# FOCDriver.net
KiCad netlist of a schematic drawn in EAGLE
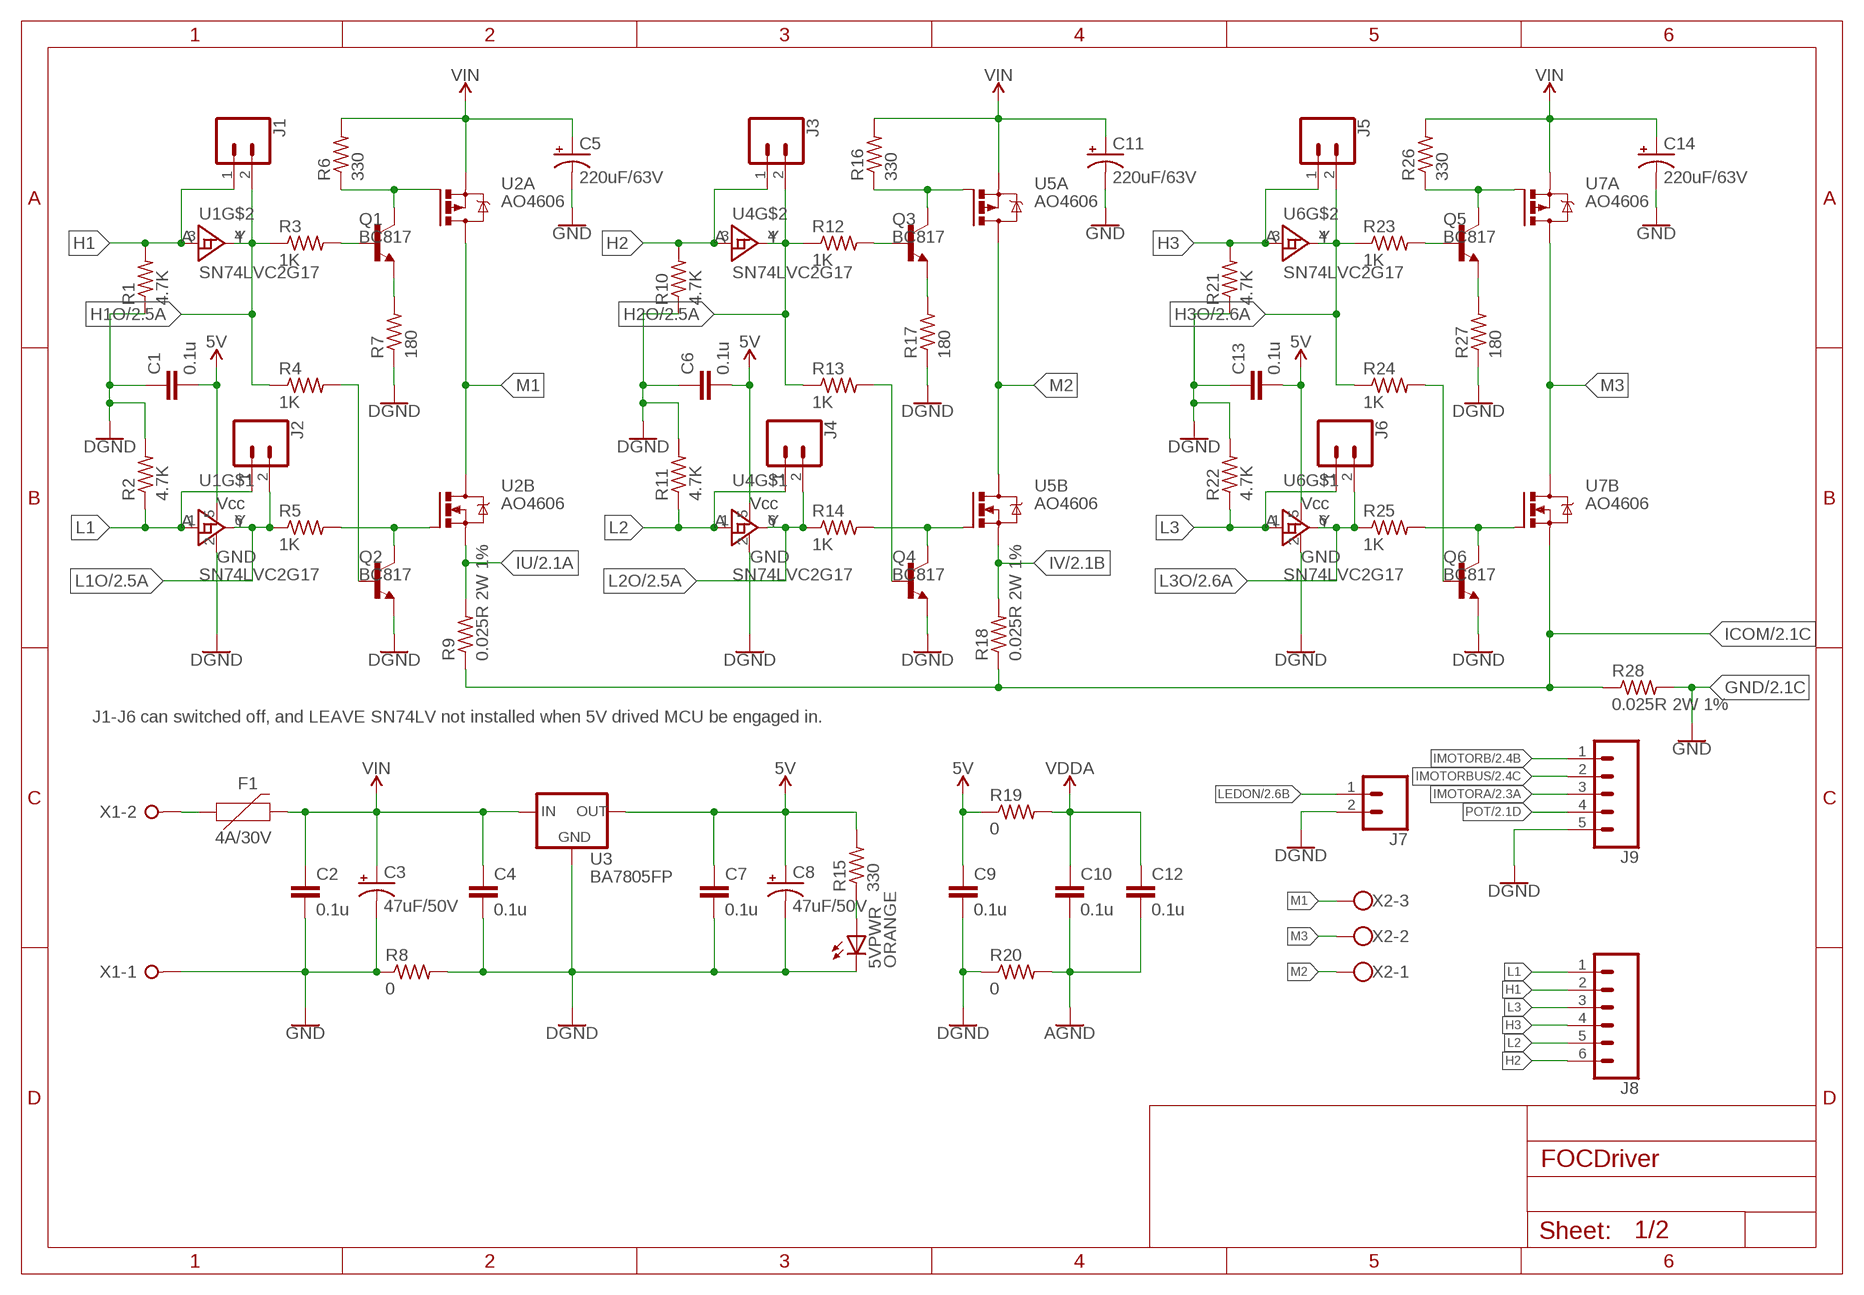
[diagram p0: schematic, sheet 1]
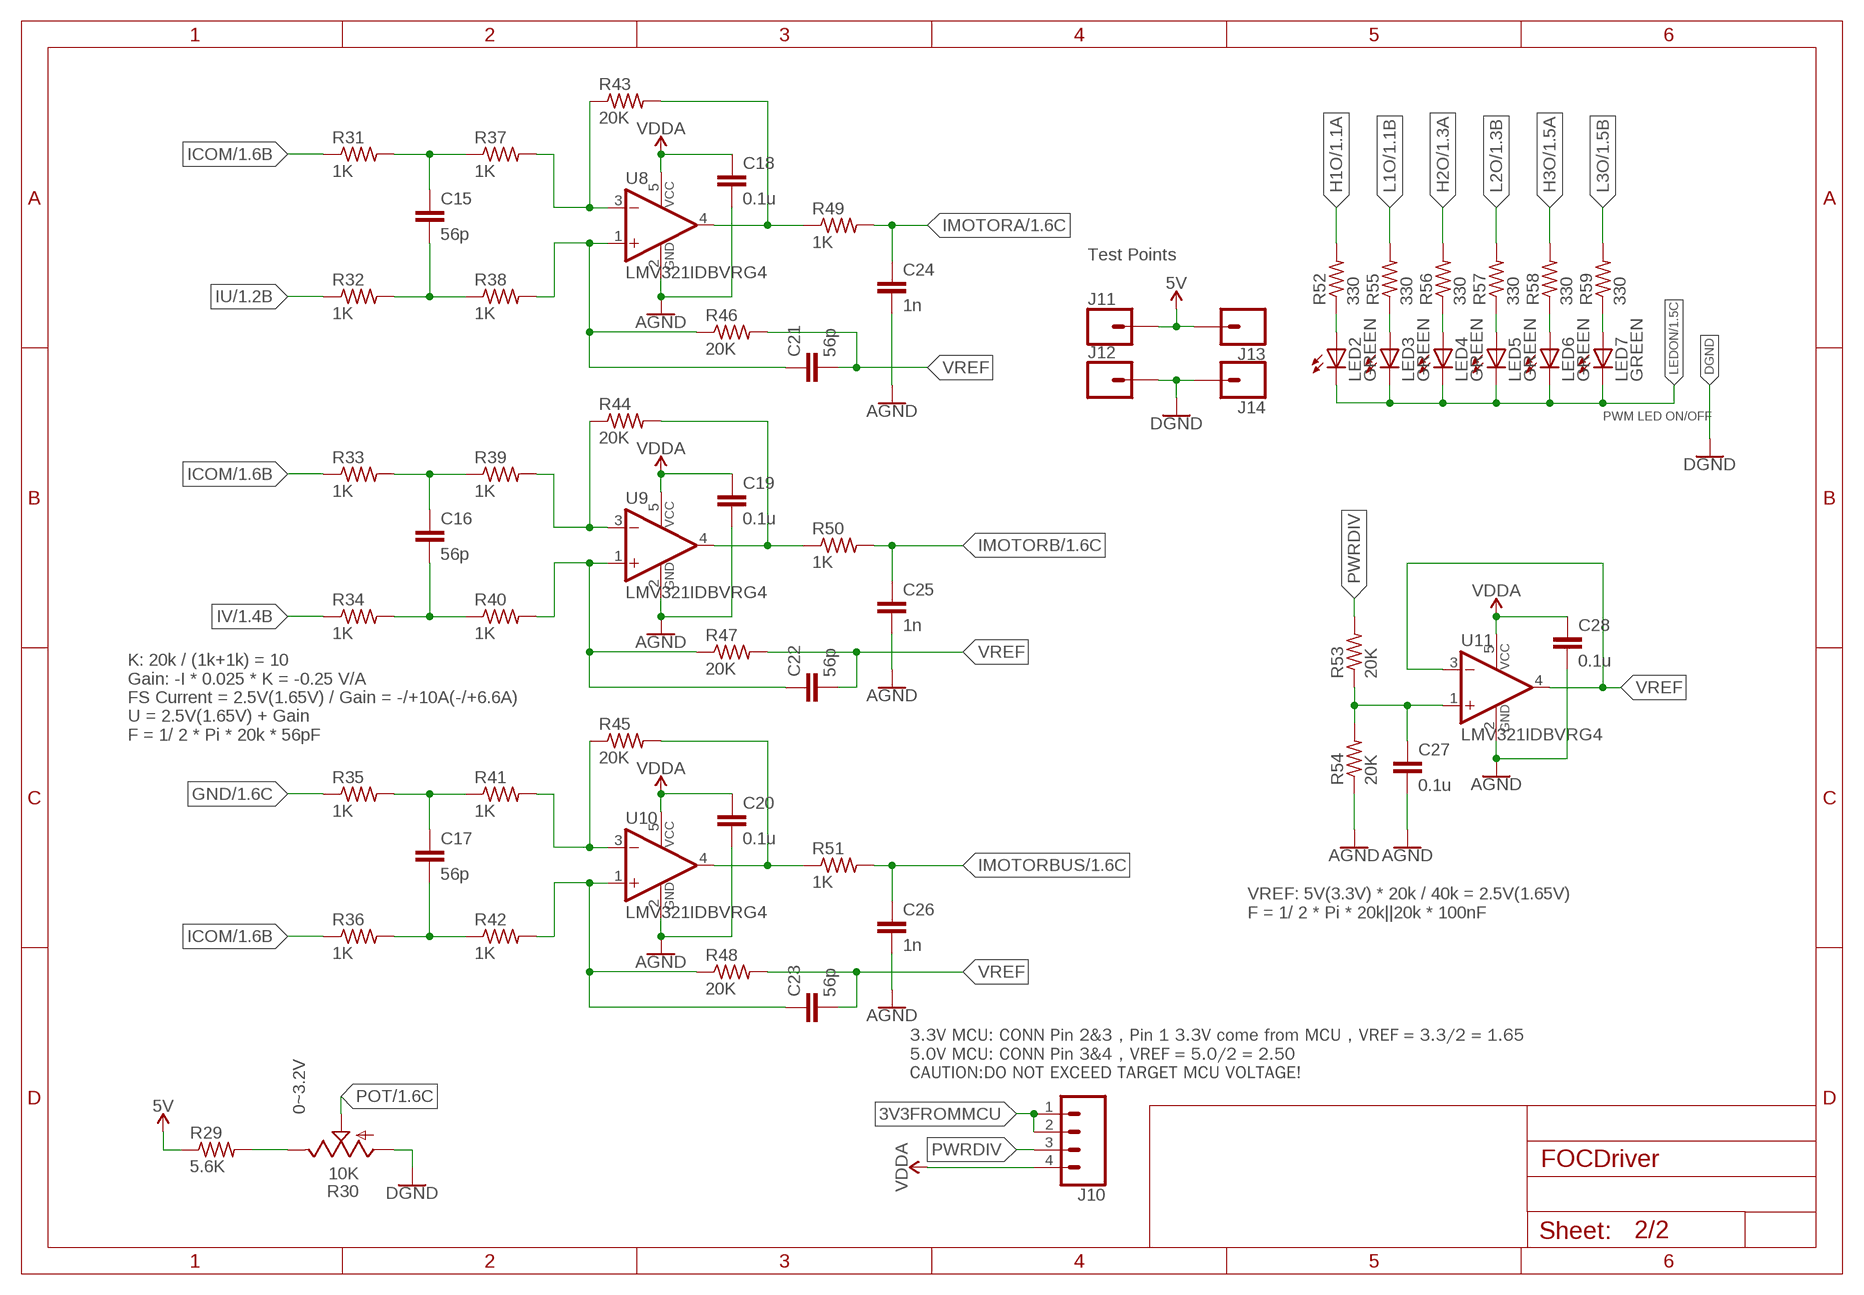
[diagram p1: schematic, sheet 2]

(export (version "E")
  (design (tool "Eeschema 10.0.6"))
  (components
    (comp (ref "C15")
      (value "56p")
      (footprint "eagle-import:C0805")
      (libsource (lib "eagle-import") (part "C-EUC0805"))
    )
    (comp (ref "C16")
      (value "56p")
      (footprint "eagle-import:C0805")
      (libsource (lib "eagle-import") (part "C-EUC0805"))
    )
    (comp (ref "C17")
      (value "56p")
      (footprint "eagle-import:C0805")
      (libsource (lib "eagle-import") (part "C-EUC0805"))
    )
    (comp (ref "C18")
      (value "0.1u")
      (footprint "eagle-import:C0805")
      (libsource (lib "eagle-import") (part "C-EUC0805"))
    )
    (comp (ref "C19")
      (value "0.1u")
      (footprint "eagle-import:C0805")
      (libsource (lib "eagle-import") (part "C-EUC0805"))
    )
    (comp (ref "C20")
      (value "0.1u")
      (footprint "eagle-import:C0805")
      (libsource (lib "eagle-import") (part "C-EUC0805"))
    )
    (comp (ref "C21")
      (value "56p")
      (footprint "eagle-import:C0805")
      (libsource (lib "eagle-import") (part "C-EUC0805"))
    )
    (comp (ref "C22")
      (value "56p")
      (footprint "eagle-import:C0805")
      (libsource (lib "eagle-import") (part "C-EUC0805"))
    )
    (comp (ref "C23")
      (value "56p")
      (footprint "eagle-import:C0805")
      (libsource (lib "eagle-import") (part "C-EUC0805"))
    )
    (comp (ref "C24")
      (value "1n")
      (footprint "eagle-import:C0805")
      (libsource (lib "eagle-import") (part "C-EUC0805"))
    )
    (comp (ref "C25")
      (value "1n")
      (footprint "eagle-import:C0805")
      (libsource (lib "eagle-import") (part "C-EUC0805"))
    )
    (comp (ref "C26")
      (value "1n")
      (footprint "eagle-import:C0805")
      (libsource (lib "eagle-import") (part "C-EUC0805"))
    )
    (comp (ref "C27")
      (value "0.1u")
      (footprint "eagle-import:C0805")
      (libsource (lib "eagle-import") (part "C-EUC0805"))
    )
    (comp (ref "C28")
      (value "0.1u")
      (footprint "eagle-import:C0805")
      (libsource (lib "eagle-import") (part "C-EUC0805"))
    )
    (comp (ref "J10")
      (value "CONN_04")
      (footprint "eagle-import:1X04")
      (libsource (lib "eagle-import") (part "CONN_04"))
    )
    (comp (ref "J11")
      (value "CONN_01PTH_NO_SILK_YES_STOP")
      (footprint "eagle-import:1X01_NO_SILK")
      (libsource (lib "eagle-import") (part "CONN_01PTH_NO_SILK_YES_STOP"))
    )
    (comp (ref "J12")
      (value "CONN_01PTH_NO_SILK_YES_STOP")
      (footprint "eagle-import:1X01_NO_SILK")
      (libsource (lib "eagle-import") (part "CONN_01PTH_NO_SILK_YES_STOP"))
    )
    (comp (ref "J13")
      (value "CONN_01PTH_NO_SILK_YES_STOP")
      (footprint "eagle-import:1X01_NO_SILK")
      (libsource (lib "eagle-import") (part "CONN_01PTH_NO_SILK_YES_STOP"))
    )
    (comp (ref "J14")
      (value "CONN_01PTH_NO_SILK_YES_STOP")
      (footprint "eagle-import:1X01_NO_SILK")
      (libsource (lib "eagle-import") (part "CONN_01PTH_NO_SILK_YES_STOP"))
    )
    (comp (ref "LED2")
      (value "GREEN")
      (footprint "eagle-import:SML0805")
      (libsource (lib "eagle-import") (part "LEDSML0805"))
    )
    (comp (ref "LED3")
      (value "GREEN")
      (footprint "eagle-import:SML0805")
      (libsource (lib "eagle-import") (part "LEDSML0805"))
    )
    (comp (ref "LED4")
      (value "GREEN")
      (footprint "eagle-import:SML0805")
      (libsource (lib "eagle-import") (part "LEDSML0805"))
    )
    (comp (ref "LED5")
      (value "GREEN")
      (footprint "eagle-import:SML0805")
      (libsource (lib "eagle-import") (part "LEDSML0805"))
    )
    (comp (ref "LED6")
      (value "GREEN")
      (footprint "eagle-import:SML0805")
      (libsource (lib "eagle-import") (part "LEDSML0805"))
    )
    (comp (ref "LED7")
      (value "GREEN")
      (footprint "eagle-import:SML0805")
      (libsource (lib "eagle-import") (part "LEDSML0805"))
    )
    (comp (ref "R29")
      (value "5.6K")
      (footprint "eagle-import:R0805")
      (libsource (lib "eagle-import") (part "R-US_R0805"))
    )
    (comp (ref "R30")
      (value "10K")
      (footprint "eagle-import:CT6")
      (libsource (lib "eagle-import") (part "TRIM_US-CT6"))
    )
    (comp (ref "R31")
      (value "1K")
      (footprint "eagle-import:R0805")
      (libsource (lib "eagle-import") (part "R-US_R0805"))
    )
    (comp (ref "R32")
      (value "1K")
      (footprint "eagle-import:R0805")
      (libsource (lib "eagle-import") (part "R-US_R0805"))
    )
    (comp (ref "R33")
      (value "1K")
      (footprint "eagle-import:R0805")
      (libsource (lib "eagle-import") (part "R-US_R0805"))
    )
    (comp (ref "R34")
      (value "1K")
      (footprint "eagle-import:R0805")
      (libsource (lib "eagle-import") (part "R-US_R0805"))
    )
    (comp (ref "R35")
      (value "1K")
      (footprint "eagle-import:R0805")
      (libsource (lib "eagle-import") (part "R-US_R0805"))
    )
    (comp (ref "R36")
      (value "1K")
      (footprint "eagle-import:R0805")
      (libsource (lib "eagle-import") (part "R-US_R0805"))
    )
    (comp (ref "R37")
      (value "1K")
      (footprint "eagle-import:R0805")
      (libsource (lib "eagle-import") (part "R-US_R0805"))
    )
    (comp (ref "R38")
      (value "1K")
      (footprint "eagle-import:R0805")
      (libsource (lib "eagle-import") (part "R-US_R0805"))
    )
    (comp (ref "R39")
      (value "1K")
      (footprint "eagle-import:R0805")
      (libsource (lib "eagle-import") (part "R-US_R0805"))
    )
    (comp (ref "R40")
      (value "1K")
      (footprint "eagle-import:R0805")
      (libsource (lib "eagle-import") (part "R-US_R0805"))
    )
    (comp (ref "R41")
      (value "1K")
      (footprint "eagle-import:R0805")
      (libsource (lib "eagle-import") (part "R-US_R0805"))
    )
    (comp (ref "R42")
      (value "1K")
      (footprint "eagle-import:R0805")
      (libsource (lib "eagle-import") (part "R-US_R0805"))
    )
    (comp (ref "R43")
      (value "20K")
      (footprint "eagle-import:R0805")
      (libsource (lib "eagle-import") (part "R-US_R0805"))
    )
    (comp (ref "R44")
      (value "20K")
      (footprint "eagle-import:R0805")
      (libsource (lib "eagle-import") (part "R-US_R0805"))
    )
    (comp (ref "R45")
      (value "20K")
      (footprint "eagle-import:R0805")
      (libsource (lib "eagle-import") (part "R-US_R0805"))
    )
    (comp (ref "R46")
      (value "20K")
      (footprint "eagle-import:R0805")
      (libsource (lib "eagle-import") (part "R-US_R0805"))
    )
    (comp (ref "R47")
      (value "20K")
      (footprint "eagle-import:R0805")
      (libsource (lib "eagle-import") (part "R-US_R0805"))
    )
    (comp (ref "R48")
      (value "20K")
      (footprint "eagle-import:R0805")
      (libsource (lib "eagle-import") (part "R-US_R0805"))
    )
    (comp (ref "R49")
      (value "1K")
      (footprint "eagle-import:R0805")
      (libsource (lib "eagle-import") (part "R-US_R0805"))
    )
    (comp (ref "R50")
      (value "1K")
      (footprint "eagle-import:R0805")
      (libsource (lib "eagle-import") (part "R-US_R0805"))
    )
    (comp (ref "R51")
      (value "1K")
      (footprint "eagle-import:R0805")
      (libsource (lib "eagle-import") (part "R-US_R0805"))
    )
    (comp (ref "R52")
      (value "330")
      (footprint "eagle-import:R0805")
      (libsource (lib "eagle-import") (part "R-US_R0805"))
    )
    (comp (ref "R53")
      (value "20K")
      (footprint "eagle-import:R0805")
      (libsource (lib "eagle-import") (part "R-US_R0805"))
    )
    (comp (ref "R54")
      (value "20K")
      (footprint "eagle-import:R0805")
      (libsource (lib "eagle-import") (part "R-US_R0805"))
    )
    (comp (ref "R55")
      (value "330")
      (footprint "eagle-import:R0805")
      (libsource (lib "eagle-import") (part "R-US_R0805"))
    )
    (comp (ref "R56")
      (value "330")
      (footprint "eagle-import:R0805")
      (libsource (lib "eagle-import") (part "R-US_R0805"))
    )
    (comp (ref "R57")
      (value "330")
      (footprint "eagle-import:R0805")
      (libsource (lib "eagle-import") (part "R-US_R0805"))
    )
    (comp (ref "R58")
      (value "330")
      (footprint "eagle-import:R0805")
      (libsource (lib "eagle-import") (part "R-US_R0805"))
    )
    (comp (ref "R59")
      (value "330")
      (footprint "eagle-import:R0805")
      (libsource (lib "eagle-import") (part "R-US_R0805"))
    )
    (comp (ref "U8")
      (value "LMV321IDBVRG4")
      (footprint "eagle-import:SOT95P285X120-5N")
      (libsource (lib "eagle-import") (part "LMV321IDBVRG4"))
    )
    (comp (ref "U9")
      (value "LMV321IDBVRG4")
      (footprint "eagle-import:SOT95P285X120-5N")
      (libsource (lib "eagle-import") (part "LMV321IDBVRG4"))
    )
    (comp (ref "U10")
      (value "LMV321IDBVRG4")
      (footprint "eagle-import:SOT95P285X120-5N")
      (libsource (lib "eagle-import") (part "LMV321IDBVRG4"))
    )
    (comp (ref "U11")
      (value "LMV321IDBVRG4")
      (footprint "eagle-import:SOT95P285X120-5N")
      (libsource (lib "eagle-import") (part "LMV321IDBVRG4"))
    )
    (comp (ref "5VPWR")
      (value "ORANGE")
      (footprint "eagle-import:SML0805")
      (libsource (lib "eagle-import") (part "LEDSML0805"))
    )
    (comp (ref "C1")
      (value "0.1u")
      (footprint "eagle-import:C0805")
      (libsource (lib "eagle-import") (part "C-EUC0805"))
    )
    (comp (ref "C2")
      (value "0.1u")
      (footprint "eagle-import:C0805")
      (libsource (lib "eagle-import") (part "C-EUC0805"))
    )
    (comp (ref "C3")
      (value "47uF/50V")
      (footprint "eagle-import:E2,5-7")
      (libsource (lib "eagle-import") (part "CPOL-USE2.5-7"))
    )
    (comp (ref "C4")
      (value "0.1u")
      (footprint "eagle-import:C0805")
      (libsource (lib "eagle-import") (part "C-EUC0805"))
    )
    (comp (ref "C5")
      (value "220uF/63V")
      (footprint "eagle-import:E5-10,5")
      (libsource (lib "eagle-import") (part "CPOL-USE5-10.5"))
    )
    (comp (ref "C6")
      (value "0.1u")
      (footprint "eagle-import:C0805")
      (libsource (lib "eagle-import") (part "C-EUC0805"))
    )
    (comp (ref "C7")
      (value "0.1u")
      (footprint "eagle-import:C0805")
      (libsource (lib "eagle-import") (part "C-EUC0805"))
    )
    (comp (ref "C8")
      (value "47uF/50V")
      (footprint "eagle-import:E2,5-7")
      (libsource (lib "eagle-import") (part "CPOL-USE2.5-7"))
    )
    (comp (ref "C9")
      (value "0.1u")
      (footprint "eagle-import:C0805")
      (libsource (lib "eagle-import") (part "C-EUC0805"))
    )
    (comp (ref "C10")
      (value "0.1u")
      (footprint "eagle-import:C0805")
      (libsource (lib "eagle-import") (part "C-EUC0805"))
    )
    (comp (ref "C11")
      (value "220uF/63V")
      (footprint "eagle-import:E5-10,5")
      (libsource (lib "eagle-import") (part "CPOL-USE5-10.5"))
    )
    (comp (ref "C12")
      (value "0.1u")
      (footprint "eagle-import:C0805")
      (libsource (lib "eagle-import") (part "C-EUC0805"))
    )
    (comp (ref "C13")
      (value "0.1u")
      (footprint "eagle-import:C0805")
      (libsource (lib "eagle-import") (part "C-EUC0805"))
    )
    (comp (ref "C14")
      (value "220uF/63V")
      (footprint "eagle-import:E5-10,5")
      (libsource (lib "eagle-import") (part "CPOL-USE5-10.5"))
    )
    (comp (ref "F1")
      (value "4A/30V")
      (footprint "eagle-import:PTH")
      (libsource (lib "eagle-import") (part "PPTC_PTH"))
    )
    (comp (ref "J1")
      (value "CONN_02")
      (footprint "eagle-import:1X02")
      (libsource (lib "eagle-import") (part "CONN_02"))
    )
    (comp (ref "J2")
      (value "CONN_02")
      (footprint "eagle-import:1X02")
      (libsource (lib "eagle-import") (part "CONN_02"))
    )
    (comp (ref "J3")
      (value "CONN_02")
      (footprint "eagle-import:1X02")
      (libsource (lib "eagle-import") (part "CONN_02"))
    )
    (comp (ref "J4")
      (value "CONN_02")
      (footprint "eagle-import:1X02")
      (libsource (lib "eagle-import") (part "CONN_02"))
    )
    (comp (ref "J5")
      (value "CONN_02")
      (footprint "eagle-import:1X02")
      (libsource (lib "eagle-import") (part "CONN_02"))
    )
    (comp (ref "J6")
      (value "CONN_02")
      (footprint "eagle-import:1X02")
      (libsource (lib "eagle-import") (part "CONN_02"))
    )
    (comp (ref "J7")
      (value "CONN_02")
      (footprint "eagle-import:1X02")
      (libsource (lib "eagle-import") (part "CONN_02"))
    )
    (comp (ref "J8")
      (value "CONN_06SILK_FEMALE_PTH")
      (footprint "eagle-import:1X06")
      (libsource (lib "eagle-import") (part "CONN_06SILK_FEMALE_PTH"))
    )
    (comp (ref "J9")
      (value "CONN_05")
      (footprint "eagle-import:1X05")
      (libsource (lib "eagle-import") (part "CONN_05"))
    )
    (comp (ref "Q1")
      (value "BC817")
      (footprint "eagle-import:SOT23-BEC")
      (libsource (lib "eagle-import") (part "BC817SMD-40"))
    )
    (comp (ref "Q2")
      (value "BC817")
      (footprint "eagle-import:SOT23-BEC")
      (libsource (lib "eagle-import") (part "BC817SMD-40"))
    )
    (comp (ref "Q3")
      (value "BC817")
      (footprint "eagle-import:SOT23-BEC")
      (libsource (lib "eagle-import") (part "BC817SMD-40"))
    )
    (comp (ref "Q4")
      (value "BC817")
      (footprint "eagle-import:SOT23-BEC")
      (libsource (lib "eagle-import") (part "BC817SMD-40"))
    )
    (comp (ref "Q5")
      (value "BC817")
      (footprint "eagle-import:SOT23-BEC")
      (libsource (lib "eagle-import") (part "BC817SMD-40"))
    )
    (comp (ref "Q6")
      (value "BC817")
      (footprint "eagle-import:SOT23-BEC")
      (libsource (lib "eagle-import") (part "BC817SMD-40"))
    )
    (comp (ref "R1")
      (value "4.7K")
      (footprint "eagle-import:R0805")
      (libsource (lib "eagle-import") (part "R-US_R0805"))
    )
    (comp (ref "R2")
      (value "4.7K")
      (footprint "eagle-import:R0805")
      (libsource (lib "eagle-import") (part "R-US_R0805"))
    )
    (comp (ref "R3")
      (value "1K")
      (footprint "eagle-import:R0805")
      (libsource (lib "eagle-import") (part "R-US_R0805"))
    )
    (comp (ref "R4")
      (value "1K")
      (footprint "eagle-import:R0805")
      (libsource (lib "eagle-import") (part "R-US_R0805"))
    )
    (comp (ref "R5")
      (value "1K")
      (footprint "eagle-import:R0805")
      (libsource (lib "eagle-import") (part "R-US_R0805"))
    )
    (comp (ref "R6")
      (value "330")
      (footprint "eagle-import:R0805")
      (libsource (lib "eagle-import") (part "R-US_R0805"))
    )
    (comp (ref "R7")
      (value "180")
      (footprint "eagle-import:R0805")
      (libsource (lib "eagle-import") (part "R-US_R0805"))
    )
    (comp (ref "R8")
      (value "0")
      (footprint "eagle-import:R0805")
      (libsource (lib "eagle-import") (part "R-US_R0805"))
    )
    (comp (ref "R9")
      (value "0.025R 2W 1%")
      (footprint "eagle-import:R2512")
      (libsource (lib "eagle-import") (part "resistor_R-US_R2512"))
    )
    (comp (ref "R10")
      (value "4.7K")
      (footprint "eagle-import:R0805")
      (libsource (lib "eagle-import") (part "R-US_R0805"))
    )
    (comp (ref "R11")
      (value "4.7K")
      (footprint "eagle-import:R0805")
      (libsource (lib "eagle-import") (part "R-US_R0805"))
    )
    (comp (ref "R12")
      (value "1K")
      (footprint "eagle-import:R0805")
      (libsource (lib "eagle-import") (part "R-US_R0805"))
    )
    (comp (ref "R13")
      (value "1K")
      (footprint "eagle-import:R0805")
      (libsource (lib "eagle-import") (part "R-US_R0805"))
    )
    (comp (ref "R14")
      (value "1K")
      (footprint "eagle-import:R0805")
      (libsource (lib "eagle-import") (part "R-US_R0805"))
    )
    (comp (ref "R15")
      (value "330")
      (footprint "eagle-import:R0805")
      (libsource (lib "eagle-import") (part "R-US_R0805"))
    )
    (comp (ref "R16")
      (value "330")
      (footprint "eagle-import:R0805")
      (libsource (lib "eagle-import") (part "R-US_R0805"))
    )
    (comp (ref "R17")
      (value "180")
      (footprint "eagle-import:R0805")
      (libsource (lib "eagle-import") (part "R-US_R0805"))
    )
    (comp (ref "R18")
      (value "0.025R 2W 1%")
      (footprint "eagle-import:R2512")
      (libsource (lib "eagle-import") (part "resistor_R-US_R2512"))
    )
    (comp (ref "R19")
      (value "0")
      (footprint "eagle-import:R0805")
      (libsource (lib "eagle-import") (part "R-US_R0805"))
    )
    (comp (ref "R20")
      (value "0")
      (footprint "eagle-import:R0805")
      (libsource (lib "eagle-import") (part "R-US_R0805"))
    )
    (comp (ref "R21")
      (value "4.7K")
      (footprint "eagle-import:R0805")
      (libsource (lib "eagle-import") (part "R-US_R0805"))
    )
    (comp (ref "R22")
      (value "4.7K")
      (footprint "eagle-import:R0805")
      (libsource (lib "eagle-import") (part "R-US_R0805"))
    )
    (comp (ref "R23")
      (value "1K")
      (footprint "eagle-import:R0805")
      (libsource (lib "eagle-import") (part "R-US_R0805"))
    )
    (comp (ref "R24")
      (value "1K")
      (footprint "eagle-import:R0805")
      (libsource (lib "eagle-import") (part "R-US_R0805"))
    )
    (comp (ref "R25")
      (value "1K")
      (footprint "eagle-import:R0805")
      (libsource (lib "eagle-import") (part "R-US_R0805"))
    )
    (comp (ref "R26")
      (value "330")
      (footprint "eagle-import:R0805")
      (libsource (lib "eagle-import") (part "R-US_R0805"))
    )
    (comp (ref "R27")
      (value "180")
      (footprint "eagle-import:R0805")
      (libsource (lib "eagle-import") (part "R-US_R0805"))
    )
    (comp (ref "R28")
      (value "0.025R 2W 1%")
      (footprint "eagle-import:R2512")
      (libsource (lib "eagle-import") (part "resistor_R-US_R2512"))
    )
    (comp (ref "U1")
      (value "SN74LVC2G17")
      (footprint "eagle-import:SOT23-6")
      (libsource (lib "eagle-import") (part "SN74LVC2G17"))
    )
    (comp (ref "U2")
      (value "AO4606")
      (footprint "eagle-import:SO08")
      (libsource (lib "eagle-import") (part "AO4606"))
    )
    (comp (ref "U3")
      (value "BA7805FP")
      (footprint "eagle-import:TO-252")
      (libsource (lib "eagle-import") (part "V_REG_78XX7812"))
    )
    (comp (ref "U4")
      (value "SN74LVC2G17")
      (footprint "eagle-import:SOT23-6")
      (libsource (lib "eagle-import") (part "SN74LVC2G17"))
    )
    (comp (ref "U5")
      (value "AO4606")
      (footprint "eagle-import:SO08")
      (libsource (lib "eagle-import") (part "AO4606"))
    )
    (comp (ref "U6")
      (value "SN74LVC2G17")
      (footprint "eagle-import:SOT23-6")
      (libsource (lib "eagle-import") (part "SN74LVC2G17"))
    )
    (comp (ref "U7")
      (value "AO4606")
      (footprint "eagle-import:SO08")
      (libsource (lib "eagle-import") (part "AO4606"))
    )
    (comp (ref "X1")
      (value "W237-02P")
      (footprint "eagle-import:W237-132")
      (libsource (lib "eagle-import") (part "W237-02P"))
    )
    (comp (ref "X2")
      (value "W237-103")
      (footprint "eagle-import:W237-103")
      (fields (field (name "MPN") "237-103"))
      (libsource (lib "eagle-import") (part "W237-103"))
    )
  )
  (nets
    (net (code "1") (name "3V3FROMMCU") (class "Default")
      (node (ref "J10") (pin "1") (pinfunction "1_1") (pintype "passive"))
      (node (ref "J10") (pin "2") (pinfunction "2_2") (pintype "passive"))
    )
    (net (code "2") (name "5V") (class "Default")
      (node (ref "C1") (pin "2") (pinfunction "2_2") (pintype "passive"))
      (node (ref "C13") (pin "2") (pinfunction "2_2") (pintype "passive"))
      (node (ref "C6") (pin "2") (pinfunction "2_2") (pintype "passive"))
      (node (ref "C7") (pin "1") (pinfunction "1_1") (pintype "passive"))
      (node (ref "C8") (pin "+") (pinfunction "+_+") (pintype "passive"))
      (node (ref "C9") (pin "1") (pinfunction "1_1") (pintype "passive"))
      (node (ref "J11") (pin "1") (pinfunction "1_1") (pintype "passive"))
      (node (ref "J13") (pin "1") (pinfunction "1_1") (pintype "passive"))
      (node (ref "R15") (pin "2") (pinfunction "2_2") (pintype "passive"))
      (node (ref "R19") (pin "1") (pinfunction "1_1") (pintype "passive"))
      (node (ref "R29") (pin "1") (pinfunction "1_1") (pintype "passive"))
      (node (ref "U1") (pin "5") (pinfunction "VCC_5") (pintype "power_in"))
      (node (ref "U3") (pin "2") (pinfunction "OUT_2") (pintype "passive"))
      (node (ref "U4") (pin "5") (pinfunction "VCC_5") (pintype "power_in"))
      (node (ref "U6") (pin "5") (pinfunction "VCC_5") (pintype "power_in"))
    )
    (net (code "3") (name "AGND") (class "Default")
      (node (ref "C10") (pin "2") (pinfunction "2_2") (pintype "passive"))
      (node (ref "C12") (pin "2") (pinfunction "2_2") (pintype "passive"))
      (node (ref "C18") (pin "2") (pinfunction "2_2") (pintype "passive"))
      (node (ref "C19") (pin "2") (pinfunction "2_2") (pintype "passive"))
      (node (ref "C20") (pin "2") (pinfunction "2_2") (pintype "passive"))
      (node (ref "C24") (pin "2") (pinfunction "2_2") (pintype "passive"))
      (node (ref "C25") (pin "2") (pinfunction "2_2") (pintype "passive"))
      (node (ref "C26") (pin "2") (pinfunction "2_2") (pintype "passive"))
      (node (ref "C27") (pin "2") (pinfunction "2_2") (pintype "passive"))
      (node (ref "C28") (pin "2") (pinfunction "2_2") (pintype "passive"))
      (node (ref "R20") (pin "2") (pinfunction "2_2") (pintype "passive"))
      (node (ref "R54") (pin "1") (pinfunction "1_1") (pintype "passive"))
      (node (ref "U10") (pin "2") (pinfunction "GND_2") (pintype "power_in"))
      (node (ref "U11") (pin "2") (pinfunction "GND_2") (pintype "power_in"))
      (node (ref "U8") (pin "2") (pinfunction "GND_2") (pintype "power_in"))
      (node (ref "U9") (pin "2") (pinfunction "GND_2") (pintype "power_in"))
    )
    (net (code "4") (name "DGND") (class "Default")
      (node (ref "5VPWR") (pin "C") (pinfunction "C_C") (pintype "passive"))
      (node (ref "C1") (pin "1") (pinfunction "1_1") (pintype "passive"))
      (node (ref "C13") (pin "1") (pinfunction "1_1") (pintype "passive"))
      (node (ref "C4") (pin "2") (pinfunction "2_2") (pintype "passive"))
      (node (ref "C6") (pin "1") (pinfunction "1_1") (pintype "passive"))
      (node (ref "C7") (pin "2") (pinfunction "2_2") (pintype "passive"))
      (node (ref "C8") (pin "-") (pinfunction "-_-") (pintype "passive"))
      (node (ref "C9") (pin "2") (pinfunction "2_2") (pintype "passive"))
      (node (ref "J12") (pin "1") (pinfunction "1_1") (pintype "passive"))
      (node (ref "J14") (pin "1") (pinfunction "1_1") (pintype "passive"))
      (node (ref "J7") (pin "2") (pinfunction "2_2") (pintype "passive"))
      (node (ref "J9") (pin "5") (pinfunction "5_5") (pintype "passive"))
      (node (ref "Q2") (pin "E") (pinfunction "E_E") (pintype "passive"))
      (node (ref "Q4") (pin "E") (pinfunction "E_E") (pintype "passive"))
      (node (ref "Q6") (pin "E") (pinfunction "E_E") (pintype "passive"))
      (node (ref "R1") (pin "1") (pinfunction "1_1") (pintype "passive"))
      (node (ref "R10") (pin "1") (pinfunction "1_1") (pintype "passive"))
      (node (ref "R11") (pin "2") (pinfunction "2_2") (pintype "passive"))
      (node (ref "R17") (pin "1") (pinfunction "1_1") (pintype "passive"))
      (node (ref "R2") (pin "2") (pinfunction "2_2") (pintype "passive"))
      (node (ref "R20") (pin "1") (pinfunction "1_1") (pintype "passive"))
      (node (ref "R21") (pin "1") (pinfunction "1_1") (pintype "passive"))
      (node (ref "R22") (pin "2") (pinfunction "2_2") (pintype "passive"))
      (node (ref "R27") (pin "1") (pinfunction "1_1") (pintype "passive"))
      (node (ref "R30") (pin "A") (pinfunction "A_A") (pintype "passive"))
      (node (ref "R7") (pin "1") (pinfunction "1_1") (pintype "passive"))
      (node (ref "R8") (pin "2") (pinfunction "2_2") (pintype "passive"))
      (node (ref "U1") (pin "2") (pinfunction "GND_2") (pintype "passive"))
      (node (ref "U3") (pin "3") (pinfunction "GND_3") (pintype "input"))
      (node (ref "U4") (pin "2") (pinfunction "GND_2") (pintype "passive"))
      (node (ref "U6") (pin "2") (pinfunction "GND_2") (pintype "passive"))
    )
    (net (code "5") (name "GND") (class "Default")
      (node (ref "C11") (pin "-") (pinfunction "-_-") (pintype "passive"))
      (node (ref "C14") (pin "-") (pinfunction "-_-") (pintype "passive"))
      (node (ref "C2") (pin "2") (pinfunction "2_2") (pintype "passive"))
      (node (ref "C3") (pin "-") (pinfunction "-_-") (pintype "passive"))
      (node (ref "C5") (pin "-") (pinfunction "-_-") (pintype "passive"))
      (node (ref "R28") (pin "2") (pinfunction "2_2") (pintype "passive"))
      (node (ref "R35") (pin "1") (pinfunction "1_1") (pintype "passive"))
      (node (ref "R8") (pin "1") (pinfunction "1_1") (pintype "passive"))
      (node (ref "X1") (pin "1") (pinfunction "KL_1") (pintype "passive"))
    )
    (net (code "6") (name "H1") (class "Default")
      (node (ref "J1") (pin "1") (pinfunction "1_1") (pintype "passive"))
      (node (ref "J8") (pin "2") (pinfunction "2_2") (pintype "passive"))
      (node (ref "R1") (pin "2") (pinfunction "2_2") (pintype "passive"))
      (node (ref "U1") (pin "3") (pinfunction "A_3") (pintype "bidirectional"))
    )
    (net (code "7") (name "H1O") (class "Default")
      (node (ref "J1") (pin "2") (pinfunction "2_2") (pintype "passive"))
      (node (ref "R3") (pin "1") (pinfunction "1_1") (pintype "passive"))
      (node (ref "R4") (pin "1") (pinfunction "1_1") (pintype "passive"))
      (node (ref "R52") (pin "2") (pinfunction "2_2") (pintype "passive"))
      (node (ref "U1") (pin "4") (pinfunction "Y_4") (pintype "bidirectional"))
    )
    (net (code "8") (name "H2") (class "Default")
      (node (ref "J3") (pin "1") (pinfunction "1_1") (pintype "passive"))
      (node (ref "J8") (pin "6") (pinfunction "6_6") (pintype "passive"))
      (node (ref "R10") (pin "2") (pinfunction "2_2") (pintype "passive"))
      (node (ref "U4") (pin "3") (pinfunction "A_3") (pintype "bidirectional"))
    )
    (net (code "9") (name "H2O") (class "Default")
      (node (ref "J3") (pin "2") (pinfunction "2_2") (pintype "passive"))
      (node (ref "R12") (pin "1") (pinfunction "1_1") (pintype "passive"))
      (node (ref "R13") (pin "1") (pinfunction "1_1") (pintype "passive"))
      (node (ref "R56") (pin "2") (pinfunction "2_2") (pintype "passive"))
      (node (ref "U4") (pin "4") (pinfunction "Y_4") (pintype "bidirectional"))
    )
    (net (code "10") (name "H3") (class "Default")
      (node (ref "J5") (pin "1") (pinfunction "1_1") (pintype "passive"))
      (node (ref "J8") (pin "4") (pinfunction "4_4") (pintype "passive"))
      (node (ref "R21") (pin "2") (pinfunction "2_2") (pintype "passive"))
      (node (ref "U6") (pin "3") (pinfunction "A_3") (pintype "bidirectional"))
    )
    (net (code "11") (name "H3O") (class "Default")
      (node (ref "J5") (pin "2") (pinfunction "2_2") (pintype "passive"))
      (node (ref "R23") (pin "1") (pinfunction "1_1") (pintype "passive"))
      (node (ref "R24") (pin "1") (pinfunction "1_1") (pintype "passive"))
      (node (ref "R58") (pin "2") (pinfunction "2_2") (pintype "passive"))
      (node (ref "U6") (pin "4") (pinfunction "Y_4") (pintype "bidirectional"))
    )
    (net (code "12") (name "ICOM") (class "Default")
      (node (ref "R18") (pin "1") (pinfunction "1_1") (pintype "passive"))
      (node (ref "R28") (pin "1") (pinfunction "1_1") (pintype "passive"))
      (node (ref "R31") (pin "1") (pinfunction "1_1") (pintype "passive"))
      (node (ref "R33") (pin "1") (pinfunction "1_1") (pintype "passive"))
      (node (ref "R36") (pin "1") (pinfunction "1_1") (pintype "passive"))
      (node (ref "R9") (pin "1") (pinfunction "1_1") (pintype "passive"))
      (node (ref "U7") (pin "1") (pinfunction "S_1") (pintype "passive"))
    )
    (net (code "13") (name "IMOTORA") (class "Default")
      (node (ref "C24") (pin "1") (pinfunction "1_1") (pintype "passive"))
      (node (ref "J9") (pin "3") (pinfunction "3_3") (pintype "passive"))
      (node (ref "R49") (pin "2") (pinfunction "2_2") (pintype "passive"))
    )
    (net (code "14") (name "IMOTORB") (class "Default")
      (node (ref "C25") (pin "1") (pinfunction "1_1") (pintype "passive"))
      (node (ref "J9") (pin "1") (pinfunction "1_1") (pintype "passive"))
      (node (ref "R50") (pin "2") (pinfunction "2_2") (pintype "passive"))
    )
    (net (code "15") (name "IMOTORBUS") (class "Default")
      (node (ref "C26") (pin "1") (pinfunction "1_1") (pintype "passive"))
      (node (ref "J9") (pin "2") (pinfunction "2_2") (pintype "passive"))
      (node (ref "R51") (pin "2") (pinfunction "2_2") (pintype "passive"))
    )
    (net (code "16") (name "IU") (class "Default")
      (node (ref "R32") (pin "1") (pinfunction "1_1") (pintype "passive"))
      (node (ref "R9") (pin "2") (pinfunction "2_2") (pintype "passive"))
      (node (ref "U2") (pin "1") (pinfunction "S_1") (pintype "passive"))
    )
    (net (code "17") (name "IV") (class "Default")
      (node (ref "R18") (pin "2") (pinfunction "2_2") (pintype "passive"))
      (node (ref "R34") (pin "1") (pinfunction "1_1") (pintype "passive"))
      (node (ref "U5") (pin "1") (pinfunction "S_1") (pintype "passive"))
    )
    (net (code "18") (name "L1") (class "Default")
      (node (ref "J2") (pin "1") (pinfunction "1_1") (pintype "passive"))
      (node (ref "J8") (pin "1") (pinfunction "1_1") (pintype "passive"))
      (node (ref "R2") (pin "1") (pinfunction "1_1") (pintype "passive"))
      (node (ref "U1") (pin "1") (pinfunction "A_1") (pintype "bidirectional"))
    )
    (net (code "19") (name "L1O") (class "Default")
      (node (ref "J2") (pin "2") (pinfunction "2_2") (pintype "passive"))
      (node (ref "R5") (pin "1") (pinfunction "1_1") (pintype "passive"))
      (node (ref "R55") (pin "2") (pinfunction "2_2") (pintype "passive"))
      (node (ref "U1") (pin "6") (pinfunction "Y_6") (pintype "bidirectional"))
    )
    (net (code "20") (name "L2") (class "Default")
      (node (ref "J4") (pin "1") (pinfunction "1_1") (pintype "passive"))
      (node (ref "J8") (pin "5") (pinfunction "5_5") (pintype "passive"))
      (node (ref "R11") (pin "1") (pinfunction "1_1") (pintype "passive"))
      (node (ref "U4") (pin "1") (pinfunction "A_1") (pintype "bidirectional"))
    )
    (net (code "21") (name "L2O") (class "Default")
      (node (ref "J4") (pin "2") (pinfunction "2_2") (pintype "passive"))
      (node (ref "R14") (pin "1") (pinfunction "1_1") (pintype "passive"))
      (node (ref "R57") (pin "2") (pinfunction "2_2") (pintype "passive"))
      (node (ref "U4") (pin "6") (pinfunction "Y_6") (pintype "bidirectional"))
    )
    (net (code "22") (name "L3") (class "Default")
      (node (ref "J6") (pin "1") (pinfunction "1_1") (pintype "passive"))
      (node (ref "J8") (pin "3") (pinfunction "3_3") (pintype "passive"))
      (node (ref "R22") (pin "1") (pinfunction "1_1") (pintype "passive"))
      (node (ref "U6") (pin "1") (pinfunction "A_1") (pintype "bidirectional"))
    )
    (net (code "23") (name "L3O") (class "Default")
      (node (ref "J6") (pin "2") (pinfunction "2_2") (pintype "passive"))
      (node (ref "R25") (pin "1") (pinfunction "1_1") (pintype "passive"))
      (node (ref "R59") (pin "2") (pinfunction "2_2") (pintype "passive"))
      (node (ref "U6") (pin "6") (pinfunction "Y_6") (pintype "bidirectional"))
    )
    (net (code "24") (name "LEDON") (class "Default")
      (node (ref "J7") (pin "1") (pinfunction "1_1") (pintype "passive"))
      (node (ref "LED2") (pin "C") (pinfunction "C_C") (pintype "passive"))
      (node (ref "LED3") (pin "C") (pinfunction "C_C") (pintype "passive"))
      (node (ref "LED4") (pin "C") (pinfunction "C_C") (pintype "passive"))
      (node (ref "LED5") (pin "C") (pinfunction "C_C") (pintype "passive"))
      (node (ref "LED6") (pin "C") (pinfunction "C_C") (pintype "passive"))
      (node (ref "LED7") (pin "C") (pinfunction "C_C") (pintype "passive"))
    )
    (net (code "25") (name "M1") (class "Default")
      (node (ref "U2") (pin "5") (pinfunction "D_5") (pintype "passive"))
      (node (ref "U2") (pin "6") (pinfunction "D_6") (pintype "passive"))
      (node (ref "U2") (pin "7") (pinfunction "D_7") (pintype "passive"))
      (node (ref "U2") (pin "8") (pinfunction "D_8") (pintype "passive"))
      (node (ref "X2") (pin "3") (pinfunction "KL_3") (pintype "passive"))
    )
    (net (code "26") (name "M2") (class "Default")
      (node (ref "U5") (pin "5") (pinfunction "D_5") (pintype "passive"))
      (node (ref "U5") (pin "6") (pinfunction "D_6") (pintype "passive"))
      (node (ref "U5") (pin "7") (pinfunction "D_7") (pintype "passive"))
      (node (ref "U5") (pin "8") (pinfunction "D_8") (pintype "passive"))
      (node (ref "X2") (pin "1") (pinfunction "KL_1") (pintype "passive"))
    )
    (net (code "27") (name "M3") (class "Default")
      (node (ref "U7") (pin "5") (pinfunction "D_5") (pintype "passive"))
      (node (ref "U7") (pin "6") (pinfunction "D_6") (pintype "passive"))
      (node (ref "U7") (pin "7") (pinfunction "D_7") (pintype "passive"))
      (node (ref "U7") (pin "8") (pinfunction "D_8") (pintype "passive"))
      (node (ref "X2") (pin "2") (pinfunction "KL_2") (pintype "passive"))
    )
    (net (code "28") (name "Net-(5VPWR-PadA)") (class "Default")
      (node (ref "5VPWR") (pin "A") (pinfunction "A_A") (pintype "passive"))
      (node (ref "R15") (pin "1") (pinfunction "1_1") (pintype "passive"))
    )
    (net (code "29") (name "Net-(C15-Pad1)") (class "Default")
      (node (ref "C15") (pin "1") (pinfunction "1_1") (pintype "passive"))
      (node (ref "R31") (pin "2") (pinfunction "2_2") (pintype "passive"))
      (node (ref "R37") (pin "1") (pinfunction "1_1") (pintype "passive"))
    )
    (net (code "30") (name "Net-(C15-Pad2)") (class "Default")
      (node (ref "C15") (pin "2") (pinfunction "2_2") (pintype "passive"))
      (node (ref "R32") (pin "2") (pinfunction "2_2") (pintype "passive"))
      (node (ref "R38") (pin "1") (pinfunction "1_1") (pintype "passive"))
    )
    (net (code "31") (name "Net-(C16-Pad1)") (class "Default")
      (node (ref "C16") (pin "1") (pinfunction "1_1") (pintype "passive"))
      (node (ref "R33") (pin "2") (pinfunction "2_2") (pintype "passive"))
      (node (ref "R39") (pin "1") (pinfunction "1_1") (pintype "passive"))
    )
    (net (code "32") (name "Net-(C16-Pad2)") (class "Default")
      (node (ref "C16") (pin "2") (pinfunction "2_2") (pintype "passive"))
      (node (ref "R34") (pin "2") (pinfunction "2_2") (pintype "passive"))
      (node (ref "R40") (pin "1") (pinfunction "1_1") (pintype "passive"))
    )
    (net (code "33") (name "Net-(C17-Pad1)") (class "Default")
      (node (ref "C17") (pin "1") (pinfunction "1_1") (pintype "passive"))
      (node (ref "R35") (pin "2") (pinfunction "2_2") (pintype "passive"))
      (node (ref "R41") (pin "1") (pinfunction "1_1") (pintype "passive"))
    )
    (net (code "34") (name "Net-(C17-Pad2)") (class "Default")
      (node (ref "C17") (pin "2") (pinfunction "2_2") (pintype "passive"))
      (node (ref "R36") (pin "2") (pinfunction "2_2") (pintype "passive"))
      (node (ref "R42") (pin "1") (pinfunction "1_1") (pintype "passive"))
    )
    (net (code "35") (name "Net-(F1-1)") (class "Default")
      (node (ref "F1") (pin "P$1") (pinfunction "1_P$1") (pintype "bidirectional"))
      (node (ref "X1") (pin "2") (pinfunction "KL_2") (pintype "passive"))
    )
    (net (code "36") (name "Net-(LED2-PadA)") (class "Default")
      (node (ref "LED2") (pin "A") (pinfunction "A_A") (pintype "passive"))
      (node (ref "R52") (pin "1") (pinfunction "1_1") (pintype "passive"))
    )
    (net (code "37") (name "Net-(LED3-PadA)") (class "Default")
      (node (ref "LED3") (pin "A") (pinfunction "A_A") (pintype "passive"))
      (node (ref "R55") (pin "1") (pinfunction "1_1") (pintype "passive"))
    )
    (net (code "38") (name "Net-(LED4-PadA)") (class "Default")
      (node (ref "LED4") (pin "A") (pinfunction "A_A") (pintype "passive"))
      (node (ref "R56") (pin "1") (pinfunction "1_1") (pintype "passive"))
    )
    (net (code "39") (name "Net-(LED5-PadA)") (class "Default")
      (node (ref "LED5") (pin "A") (pinfunction "A_A") (pintype "passive"))
      (node (ref "R57") (pin "1") (pinfunction "1_1") (pintype "passive"))
    )
    (net (code "40") (name "Net-(LED6-PadA)") (class "Default")
      (node (ref "LED6") (pin "A") (pinfunction "A_A") (pintype "passive"))
      (node (ref "R58") (pin "1") (pinfunction "1_1") (pintype "passive"))
    )
    (net (code "41") (name "Net-(LED7-PadA)") (class "Default")
      (node (ref "LED7") (pin "A") (pinfunction "A_A") (pintype "passive"))
      (node (ref "R59") (pin "1") (pinfunction "1_1") (pintype "passive"))
    )
    (net (code "42") (name "Net-(Q1-PadB)") (class "Default")
      (node (ref "Q1") (pin "B") (pinfunction "B_B") (pintype "passive"))
      (node (ref "R3") (pin "2") (pinfunction "2_2") (pintype "passive"))
    )
    (net (code "43") (name "Net-(Q1-PadE)") (class "Default")
      (node (ref "Q1") (pin "E") (pinfunction "E_E") (pintype "passive"))
      (node (ref "R7") (pin "2") (pinfunction "2_2") (pintype "passive"))
    )
    (net (code "44") (name "Net-(Q2-PadB)") (class "Default")
      (node (ref "Q2") (pin "B") (pinfunction "B_B") (pintype "passive"))
      (node (ref "R4") (pin "2") (pinfunction "2_2") (pintype "passive"))
    )
    (net (code "45") (name "Net-(Q3-PadB)") (class "Default")
      (node (ref "Q3") (pin "B") (pinfunction "B_B") (pintype "passive"))
      (node (ref "R12") (pin "2") (pinfunction "2_2") (pintype "passive"))
    )
    (net (code "46") (name "Net-(Q3-PadE)") (class "Default")
      (node (ref "Q3") (pin "E") (pinfunction "E_E") (pintype "passive"))
      (node (ref "R17") (pin "2") (pinfunction "2_2") (pintype "passive"))
    )
    (net (code "47") (name "Net-(Q4-PadB)") (class "Default")
      (node (ref "Q4") (pin "B") (pinfunction "B_B") (pintype "passive"))
      (node (ref "R13") (pin "2") (pinfunction "2_2") (pintype "passive"))
    )
    (net (code "48") (name "Net-(Q5-PadB)") (class "Default")
      (node (ref "Q5") (pin "B") (pinfunction "B_B") (pintype "passive"))
      (node (ref "R23") (pin "2") (pinfunction "2_2") (pintype "passive"))
    )
    (net (code "49") (name "Net-(Q5-PadE)") (class "Default")
      (node (ref "Q5") (pin "E") (pinfunction "E_E") (pintype "passive"))
      (node (ref "R27") (pin "2") (pinfunction "2_2") (pintype "passive"))
    )
    (net (code "50") (name "Net-(Q6-PadB)") (class "Default")
      (node (ref "Q6") (pin "B") (pinfunction "B_B") (pintype "passive"))
      (node (ref "R24") (pin "2") (pinfunction "2_2") (pintype "passive"))
    )
    (net (code "51") (name "Net-(R29-Pad2)") (class "Default")
      (node (ref "R29") (pin "2") (pinfunction "2_2") (pintype "passive"))
      (node (ref "R30") (pin "E") (pinfunction "E_E") (pintype "passive"))
    )
    (net (code "52") (name "Net-(U2A-G)") (class "Default")
      (node (ref "Q1") (pin "C") (pinfunction "C_C") (pintype "passive"))
      (node (ref "R6") (pin "1") (pinfunction "1_1") (pintype "passive"))
      (node (ref "U2") (pin "4") (pinfunction "G_4") (pintype "passive"))
    )
    (net (code "53") (name "Net-(U2B-G)") (class "Default")
      (node (ref "Q2") (pin "C") (pinfunction "C_C") (pintype "passive"))
      (node (ref "R5") (pin "2") (pinfunction "2_2") (pintype "passive"))
      (node (ref "U2") (pin "2") (pinfunction "G_2") (pintype "passive"))
    )
    (net (code "54") (name "Net-(U5A-G)") (class "Default")
      (node (ref "Q3") (pin "C") (pinfunction "C_C") (pintype "passive"))
      (node (ref "R16") (pin "1") (pinfunction "1_1") (pintype "passive"))
      (node (ref "U5") (pin "4") (pinfunction "G_4") (pintype "passive"))
    )
    (net (code "55") (name "Net-(U5B-G)") (class "Default")
      (node (ref "Q4") (pin "C") (pinfunction "C_C") (pintype "passive"))
      (node (ref "R14") (pin "2") (pinfunction "2_2") (pintype "passive"))
      (node (ref "U5") (pin "2") (pinfunction "G_2") (pintype "passive"))
    )
    (net (code "56") (name "Net-(U7A-G)") (class "Default")
      (node (ref "Q5") (pin "C") (pinfunction "C_C") (pintype "passive"))
      (node (ref "R26") (pin "1") (pinfunction "1_1") (pintype "passive"))
      (node (ref "U7") (pin "4") (pinfunction "G_4") (pintype "passive"))
    )
    (net (code "57") (name "Net-(U7B-G)") (class "Default")
      (node (ref "Q6") (pin "C") (pinfunction "C_C") (pintype "passive"))
      (node (ref "R25") (pin "2") (pinfunction "2_2") (pintype "passive"))
      (node (ref "U7") (pin "2") (pinfunction "G_2") (pintype "passive"))
    )
    (net (code "58") (name "Net-(U8-+IN)") (class "Default")
      (node (ref "C21") (pin "1") (pinfunction "1_1") (pintype "passive"))
      (node (ref "R38") (pin "2") (pinfunction "2_2") (pintype "passive"))
      (node (ref "R46") (pin "1") (pinfunction "1_1") (pintype "passive"))
      (node (ref "U8") (pin "1") (pinfunction "+IN_1") (pintype "input"))
    )
    (net (code "59") (name "Net-(U8--IN)") (class "Default")
      (node (ref "R37") (pin "2") (pinfunction "2_2") (pintype "passive"))
      (node (ref "R43") (pin "1") (pinfunction "1_1") (pintype "passive"))
      (node (ref "U8") (pin "3") (pinfunction "-IN_3") (pintype "input"))
    )
    (net (code "60") (name "Net-(U8-OUT)") (class "Default")
      (node (ref "R43") (pin "2") (pinfunction "2_2") (pintype "passive"))
      (node (ref "R49") (pin "1") (pinfunction "1_1") (pintype "passive"))
      (node (ref "U8") (pin "4") (pinfunction "OUT_4") (pintype "output"))
    )
    (net (code "61") (name "Net-(U9-+IN)") (class "Default")
      (node (ref "C22") (pin "1") (pinfunction "1_1") (pintype "passive"))
      (node (ref "R40") (pin "2") (pinfunction "2_2") (pintype "passive"))
      (node (ref "R47") (pin "1") (pinfunction "1_1") (pintype "passive"))
      (node (ref "U9") (pin "1") (pinfunction "+IN_1") (pintype "input"))
    )
    (net (code "62") (name "Net-(U9--IN)") (class "Default")
      (node (ref "R39") (pin "2") (pinfunction "2_2") (pintype "passive"))
      (node (ref "R44") (pin "1") (pinfunction "1_1") (pintype "passive"))
      (node (ref "U9") (pin "3") (pinfunction "-IN_3") (pintype "input"))
    )
    (net (code "63") (name "Net-(U9-OUT)") (class "Default")
      (node (ref "R44") (pin "2") (pinfunction "2_2") (pintype "passive"))
      (node (ref "R50") (pin "1") (pinfunction "1_1") (pintype "passive"))
      (node (ref "U9") (pin "4") (pinfunction "OUT_4") (pintype "output"))
    )
    (net (code "64") (name "Net-(U10-+IN)") (class "Default")
      (node (ref "C23") (pin "1") (pinfunction "1_1") (pintype "passive"))
      (node (ref "R42") (pin "2") (pinfunction "2_2") (pintype "passive"))
      (node (ref "R48") (pin "1") (pinfunction "1_1") (pintype "passive"))
      (node (ref "U10") (pin "1") (pinfunction "+IN_1") (pintype "input"))
    )
    (net (code "65") (name "Net-(U10--IN)") (class "Default")
      (node (ref "R41") (pin "2") (pinfunction "2_2") (pintype "passive"))
      (node (ref "R45") (pin "1") (pinfunction "1_1") (pintype "passive"))
      (node (ref "U10") (pin "3") (pinfunction "-IN_3") (pintype "input"))
    )
    (net (code "66") (name "Net-(U10-OUT)") (class "Default")
      (node (ref "R45") (pin "2") (pinfunction "2_2") (pintype "passive"))
      (node (ref "R51") (pin "1") (pinfunction "1_1") (pintype "passive"))
      (node (ref "U10") (pin "4") (pinfunction "OUT_4") (pintype "output"))
    )
    (net (code "67") (name "Net-(U11-+IN)") (class "Default")
      (node (ref "C27") (pin "1") (pinfunction "1_1") (pintype "passive"))
      (node (ref "R53") (pin "1") (pinfunction "1_1") (pintype "passive"))
      (node (ref "R54") (pin "2") (pinfunction "2_2") (pintype "passive"))
      (node (ref "U11") (pin "1") (pinfunction "+IN_1") (pintype "input"))
    )
    (net (code "68") (name "POT") (class "Default")
      (node (ref "J9") (pin "4") (pinfunction "4_4") (pintype "passive"))
      (node (ref "R30") (pin "S") (pinfunction "S_S") (pintype "passive"))
    )
    (net (code "69") (name "PWRDIV") (class "Default")
      (node (ref "J10") (pin "3") (pinfunction "3_3") (pintype "passive"))
      (node (ref "R53") (pin "2") (pinfunction "2_2") (pintype "passive"))
    )
    (net (code "70") (name "VDDA") (class "Default")
      (node (ref "C10") (pin "1") (pinfunction "1_1") (pintype "passive"))
      (node (ref "C12") (pin "1") (pinfunction "1_1") (pintype "passive"))
      (node (ref "C18") (pin "1") (pinfunction "1_1") (pintype "passive"))
      (node (ref "C19") (pin "1") (pinfunction "1_1") (pintype "passive"))
      (node (ref "C20") (pin "1") (pinfunction "1_1") (pintype "passive"))
      (node (ref "C28") (pin "1") (pinfunction "1_1") (pintype "passive"))
      (node (ref "J10") (pin "4") (pinfunction "4_4") (pintype "passive"))
      (node (ref "R19") (pin "2") (pinfunction "2_2") (pintype "passive"))
      (node (ref "U10") (pin "5") (pinfunction "VCC_5") (pintype "power_in"))
      (node (ref "U11") (pin "5") (pinfunction "VCC_5") (pintype "power_in"))
      (node (ref "U8") (pin "5") (pinfunction "VCC_5") (pintype "power_in"))
      (node (ref "U9") (pin "5") (pinfunction "VCC_5") (pintype "power_in"))
    )
    (net (code "71") (name "VIN") (class "Default")
      (node (ref "C11") (pin "+") (pinfunction "+_+") (pintype "passive"))
      (node (ref "C14") (pin "+") (pinfunction "+_+") (pintype "passive"))
      (node (ref "C2") (pin "1") (pinfunction "1_1") (pintype "passive"))
      (node (ref "C3") (pin "+") (pinfunction "+_+") (pintype "passive"))
      (node (ref "C4") (pin "1") (pinfunction "1_1") (pintype "passive"))
      (node (ref "C5") (pin "+") (pinfunction "+_+") (pintype "passive"))
      (node (ref "F1") (pin "P$2") (pinfunction "2_P$2") (pintype "bidirectional"))
      (node (ref "R16") (pin "2") (pinfunction "2_2") (pintype "passive"))
      (node (ref "R26") (pin "2") (pinfunction "2_2") (pintype "passive"))
      (node (ref "R6") (pin "2") (pinfunction "2_2") (pintype "passive"))
      (node (ref "U2") (pin "3") (pinfunction "S_3") (pintype "passive"))
      (node (ref "U3") (pin "1") (pinfunction "IN_1") (pintype "input"))
      (node (ref "U5") (pin "3") (pinfunction "S_3") (pintype "passive"))
      (node (ref "U7") (pin "3") (pinfunction "S_3") (pintype "passive"))
    )
    (net (code "72") (name "VREF") (class "Default")
      (node (ref "C21") (pin "2") (pinfunction "2_2") (pintype "passive"))
      (node (ref "C22") (pin "2") (pinfunction "2_2") (pintype "passive"))
      (node (ref "C23") (pin "2") (pinfunction "2_2") (pintype "passive"))
      (node (ref "R46") (pin "2") (pinfunction "2_2") (pintype "passive"))
      (node (ref "R47") (pin "2") (pinfunction "2_2") (pintype "passive"))
      (node (ref "R48") (pin "2") (pinfunction "2_2") (pintype "passive"))
      (node (ref "U11") (pin "3") (pinfunction "-IN_3") (pintype "input"))
      (node (ref "U11") (pin "4") (pinfunction "OUT_4") (pintype "output"))
    )
  )
)
